# EDU_High-Speed-Design_CPU_PCIe.net
KiCad netlist of a schematic drawn in Altium Designer
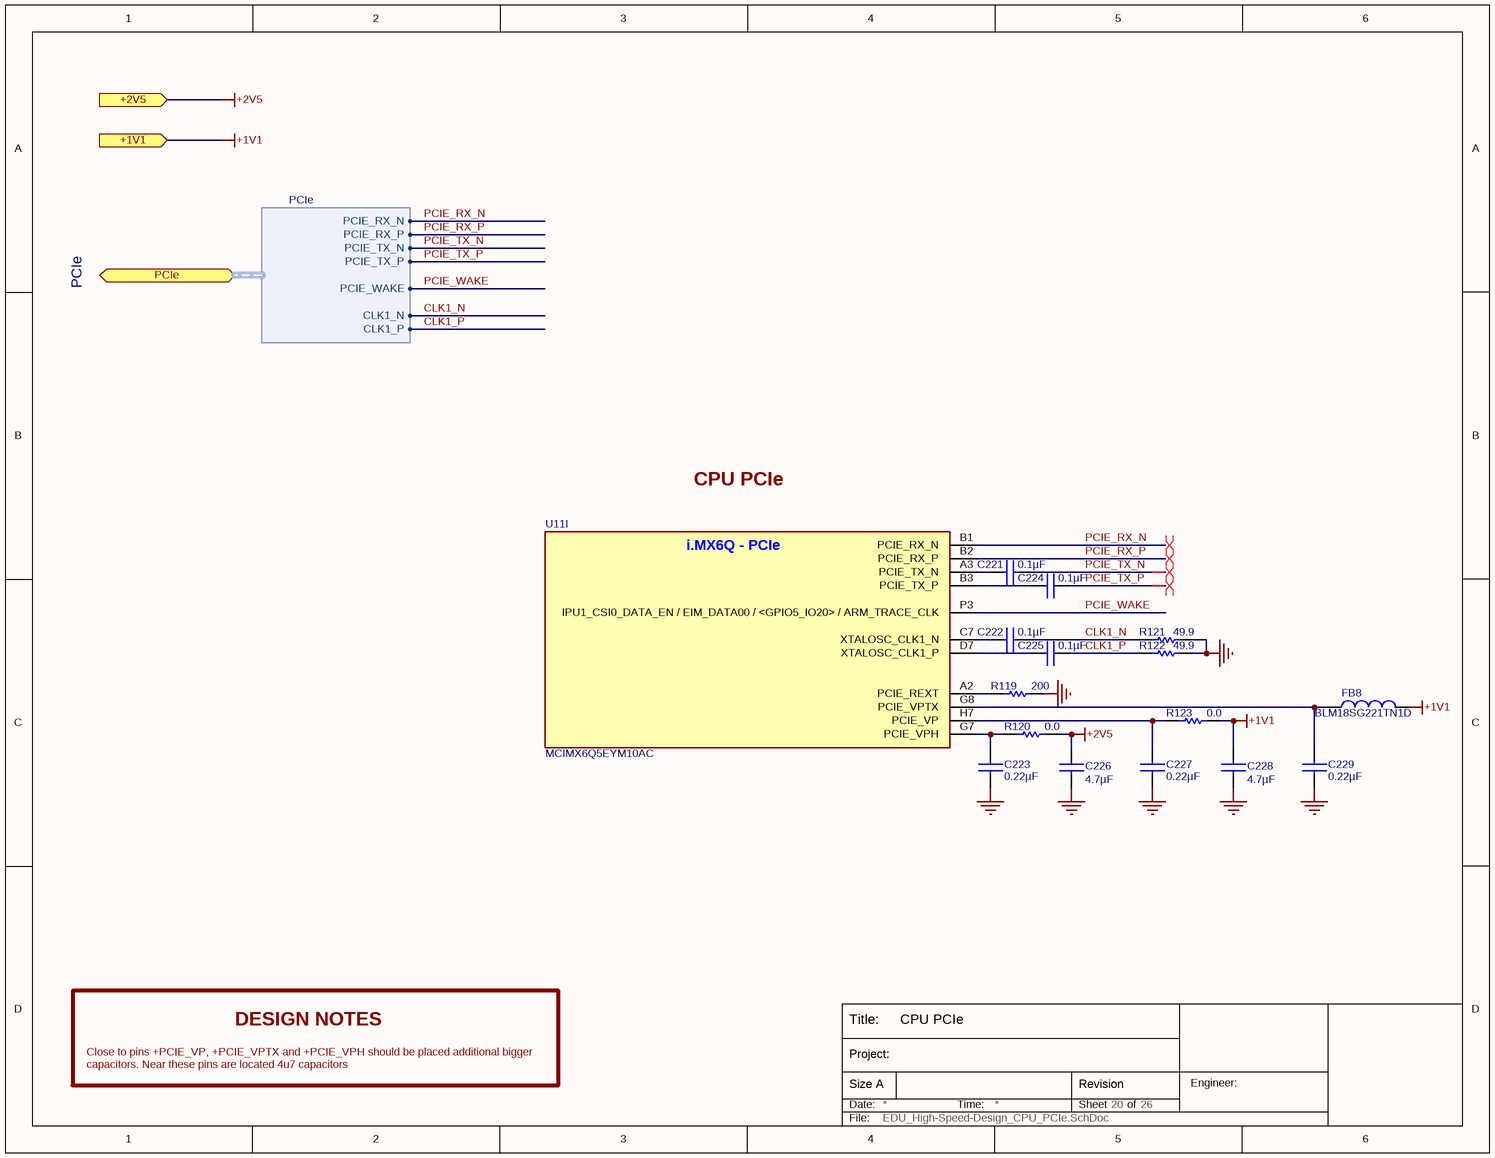
[diagram p0: EDU_High-Speed-Design_CPU_PCIe.SchDoc]

(export (version "E")
  (design (tool "Eeschema 10.0.6"))
  (components
    (comp (ref "C221")
      (value "0.1µF")
      (footprint "C0402")
      (description "CAP CER .10UF 50V X5R 10% 0402")
      (fields (field (name "VOLTAGE") "50V"))
      (libsource (lib "EDU_High-Speed-Design") (part "C1005X5R1H104K"))
    )
    (comp (ref "C222")
      (value "0.1µF")
      (footprint "C0402")
      (description "CAP CER .10UF 50V X5R 10% 0402")
      (fields (field (name "VOLTAGE") "50V"))
      (libsource (lib "EDU_High-Speed-Design") (part "C1005X5R1H104K"))
    )
    (comp (ref "C223")
      (value "0.22µF")
      (footprint "C0402")
      (description "CAP CER .22UF 25V X5R 20% 0402")
      (fields (field (name "VOLTAGE") "25V"))
      (libsource (lib "EDU_High-Speed-Design") (part "C1005X5R1E224M"))
    )
    (comp (ref "C224")
      (value "0.1µF")
      (footprint "C0402")
      (description "CAP CER .10UF 50V X5R 10% 0402")
      (fields (field (name "VOLTAGE") "50V"))
      (libsource (lib "EDU_High-Speed-Design") (part "C1005X5R1H104K"))
    )
    (comp (ref "C225")
      (value "0.1µF")
      (footprint "C0402")
      (description "CAP CER .10UF 50V X5R 10% 0402")
      (fields (field (name "VOLTAGE") "50V"))
      (libsource (lib "EDU_High-Speed-Design") (part "C1005X5R1H104K"))
    )
    (comp (ref "C226")
      (value "4.7µF")
      (footprint "C0402")
      (description "CAP CER 4.7UF 10V 20% X5R 0402")
      (fields (field (name "VOLTAGE") "10V"))
      (libsource (lib "EDU_High-Speed-Design") (part "C1005X5R1A475M"))
    )
    (comp (ref "C227")
      (value "0.22µF")
      (footprint "C0402")
      (description "CAP CER .22UF 25V X5R 20% 0402")
      (fields (field (name "VOLTAGE") "25V"))
      (libsource (lib "EDU_High-Speed-Design") (part "C1005X5R1E224M"))
    )
    (comp (ref "C228")
      (value "4.7µF")
      (footprint "C0402")
      (description "CAP CER 4.7UF 10V 20% X5R 0402")
      (fields (field (name "VOLTAGE") "10V"))
      (libsource (lib "EDU_High-Speed-Design") (part "C1005X5R1A475M"))
    )
    (comp (ref "C229")
      (value "0.22µF")
      (footprint "C0402")
      (description "CAP CER .22UF 25V X5R 20% 0402")
      (fields (field (name "VOLTAGE") "25V"))
      (libsource (lib "EDU_High-Speed-Design") (part "C1005X5R1E224M"))
    )
    (comp (ref "FB8")
      (value "BLM18SG221TN1D")
      (footprint "L0603")
      (description "FERRITE CHIP 220 OHM 2500MA 0603")
      (libsource (lib "EDU_High-Speed-Design") (part "BLM18SG221TN1D"))
    )
    (comp (ref "R119")
      (value "200")
      (footprint "R0402")
      (description "RES 200 OHM 1/16W 1% 0402 SMD")
      (libsource (lib "EDU_High-Speed-Design") (part "CRCW0402200RFKED"))
    )
    (comp (ref "R120")
      (value "0.0")
      (footprint "R0402")
      (description "RES 0.0 OHM 1/16W 0402 SMD")
      (libsource (lib "EDU_High-Speed-Design") (part "RC0402JR-070RL"))
    )
    (comp (ref "R121")
      (value "49.9")
      (footprint "R0402")
      (description "RES 49.9 OHM 1/16W 1% 0402 SMD")
      (libsource (lib "EDU_High-Speed-Design") (part "RC0402FR-0749R9L"))
    )
    (comp (ref "R122")
      (value "49.9")
      (footprint "R0402")
      (description "RES 49.9 OHM 1/16W 1% 0402 SMD")
      (libsource (lib "EDU_High-Speed-Design") (part "RC0402FR-0749R9L"))
    )
    (comp (ref "R123")
      (value "0.0")
      (footprint "R0402")
      (description "RES 0.0 OHM 1/16W 0402 SMD")
      (libsource (lib "EDU_High-Speed-Design") (part "RC0402JR-070RL"))
    )
    (comp (ref "U11")
      (value "MCIMX6Q5EYM10AC")
      (footprint "MCIMX6Q5EYM10AC")
      (description "IC MCU 32BIT ARM QUAD 624FCBGA")
      (libsource (lib "EDU_High-Speed-Design") (part "MCIMX6Q5EYM10AC"))
    )
  )
  (nets
    (net (code "2") (name "+1V1") (class "Default")
      (node (ref "C228") (pin "1") (pinfunction "1_1") (pintype "passive"))
      (node (ref "FB8") (pin "2") (pinfunction "2_2") (pintype "passive"))
      (node (ref "R123") (pin "2") (pinfunction "2_2") (pintype "passive"))
    )
    (net (code "3") (name "+2V5") (class "Default")
      (node (ref "C226") (pin "1") (pinfunction "1_1") (pintype "passive"))
      (node (ref "R120") (pin "2") (pinfunction "2_2") (pintype "passive"))
    )
    (net (code "4") (name "/CLK1_N") (class "Default")
      (node (ref "C222") (pin "2") (pinfunction "2_2") (pintype "passive"))
      (node (ref "R121") (pin "2") (pinfunction "2_2") (pintype "passive"))
    )
    (net (code "5") (name "/CLK1_P") (class "Default")
      (node (ref "C225") (pin "2") (pinfunction "2_2") (pintype "passive"))
      (node (ref "R122") (pin "2") (pinfunction "2_2") (pintype "passive"))
    )
    (net (code "6") (name "/PCIE_RX_N") (class "Default")
      (node (ref "U11") (pin "B1") (pinfunction "PCIE_RX_N_B1") (pintype "passive"))
    )
    (net (code "7") (name "/PCIE_RX_P") (class "Default")
      (node (ref "U11") (pin "B2") (pinfunction "PCIE_RX_P_B2") (pintype "passive"))
    )
    (net (code "8") (name "/PCIE_TX_N") (class "Default")
      (node (ref "C221") (pin "2") (pinfunction "2_2") (pintype "passive"))
    )
    (net (code "9") (name "/PCIE_TX_P") (class "Default")
      (node (ref "C224") (pin "2") (pinfunction "2_2") (pintype "passive"))
    )
    (net (code "10") (name "/PCIE_WAKE") (class "Default")
      (node (ref "U11") (pin "P3") (pinfunction "IPU1_CSI0_DATA_EN_/_EIM_DATA00_/_<GPIO5_IO20>_/_ARM_TRACE_CLK_P3") (pintype "passive"))
    )
    (net (code "12") (name "GND") (class "Default")
      (node (ref "C223") (pin "2") (pinfunction "2_2") (pintype "passive"))
      (node (ref "C226") (pin "2") (pinfunction "2_2") (pintype "passive"))
      (node (ref "C227") (pin "2") (pinfunction "2_2") (pintype "passive"))
      (node (ref "C228") (pin "2") (pinfunction "2_2") (pintype "passive"))
      (node (ref "C229") (pin "2") (pinfunction "2_2") (pintype "passive"))
      (node (ref "R119") (pin "1") (pinfunction "1_1") (pintype "passive"))
      (node (ref "R121") (pin "1") (pinfunction "1_1") (pintype "passive"))
      (node (ref "R122") (pin "1") (pinfunction "1_1") (pintype "passive"))
    )
    (net (code "13") (name "Net-(U11I-PCIE_REXT)") (class "Default")
      (node (ref "R119") (pin "2") (pinfunction "2_2") (pintype "passive"))
      (node (ref "U11") (pin "A2") (pinfunction "PCIE_REXT_A2") (pintype "passive"))
    )
    (net (code "14") (name "Net-(U11I-PCIE_TX_N)") (class "Default")
      (node (ref "C221") (pin "1") (pinfunction "1_1") (pintype "passive"))
      (node (ref "U11") (pin "A3") (pinfunction "PCIE_TX_N_A3") (pintype "passive"))
    )
    (net (code "15") (name "Net-(U11I-PCIE_TX_P)") (class "Default")
      (node (ref "C224") (pin "1") (pinfunction "1_1") (pintype "passive"))
      (node (ref "U11") (pin "B3") (pinfunction "PCIE_TX_P_B3") (pintype "passive"))
    )
    (net (code "16") (name "Net-(U11I-PCIE_VP)") (class "Default")
      (node (ref "C227") (pin "1") (pinfunction "1_1") (pintype "passive"))
      (node (ref "R123") (pin "1") (pinfunction "1_1") (pintype "passive"))
      (node (ref "U11") (pin "H7") (pinfunction "PCIE_VP_H7") (pintype "passive"))
    )
    (net (code "17") (name "Net-(U11I-PCIE_VPH)") (class "Default")
      (node (ref "C223") (pin "1") (pinfunction "1_1") (pintype "passive"))
      (node (ref "R120") (pin "1") (pinfunction "1_1") (pintype "passive"))
      (node (ref "U11") (pin "G7") (pinfunction "PCIE_VPH_G7") (pintype "passive"))
    )
    (net (code "18") (name "Net-(U11I-PCIE_VPTX)") (class "Default")
      (node (ref "C229") (pin "1") (pinfunction "1_1") (pintype "passive"))
      (node (ref "FB8") (pin "1") (pinfunction "1_1") (pintype "passive"))
      (node (ref "U11") (pin "G8") (pinfunction "PCIE_VPTX_G8") (pintype "passive"))
    )
    (net (code "19") (name "Net-(U11I-XTALOSC_CLK1_N)") (class "Default")
      (node (ref "C222") (pin "1") (pinfunction "1_1") (pintype "passive"))
      (node (ref "U11") (pin "C7") (pinfunction "XTALOSC_CLK1_N_C7") (pintype "passive"))
    )
    (net (code "20") (name "Net-(U11I-XTALOSC_CLK1_P)") (class "Default")
      (node (ref "C225") (pin "1") (pinfunction "1_1") (pintype "passive"))
      (node (ref "U11") (pin "D7") (pinfunction "XTALOSC_CLK1_P_D7") (pintype "passive"))
    )
  )
)
